# Sheet1.net
KiCad netlist of a schematic drawn in Altium Designer
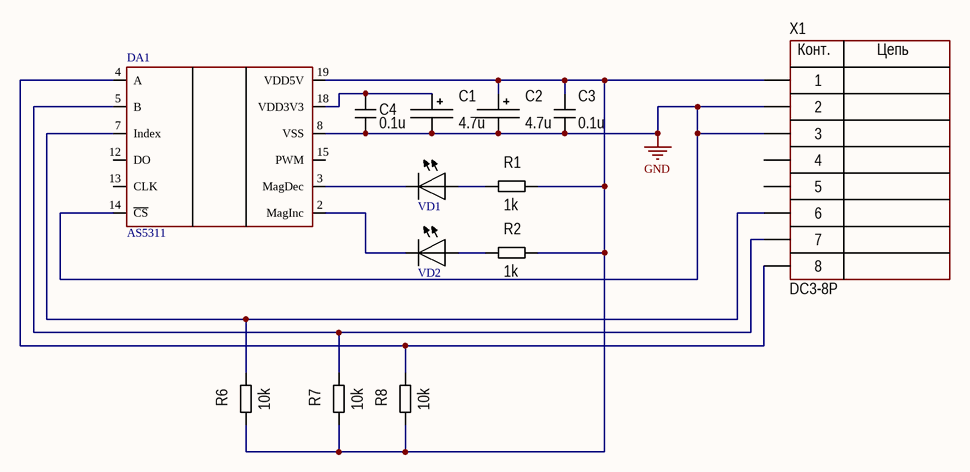
[diagram p0: Sheet1.SchDoc]

(export (version "E")
  (design (tool "Eeschema 10.0.6"))
  (components
    (comp (ref "C1")
      (value "4.7u")
      (footprint "TANTAL_A")
      (fields (field (name "MANUFACTURER") "10u"))
      (libsource (lib "Condensators") (part "TantalCap"))
    )
    (comp (ref "C2")
      (value "4.7u")
      (footprint "TANTAL_A")
      (fields (field (name "MANUFACTURER") "10u"))
      (libsource (lib "Condensators") (part "TantalCap"))
    )
    (comp (ref "C3") (value "0.1u") (footprint "CH0603C") (libsource (lib "Condensators") (part "Capacitor")))
    (comp (ref "C4") (value "0.1u") (footprint "CH0805C") (libsource (lib "Condensators") (part "Capacitor")))
    (comp (ref "DA1") (value "AS5311") (footprint "20-TSSOP") (libsource (lib "Schlib1") (part "AS5311")))
    (comp (ref "R1")
      (value "1k")
      (footprint "standard:CH0402R")
      (libsource (lib "Resistors") (part "Resistor"))
    )
    (comp (ref "R2")
      (value "1k")
      (footprint "standard:CH0402R")
      (libsource (lib "Resistors") (part "Resistor"))
    )
    (comp (ref "R6")
      (value "10k")
      (footprint "standard:CH0402R")
      (libsource (lib "Resistors") (part "Resistor"))
    )
    (comp (ref "R7")
      (value "10k")
      (footprint "standard:CH0402R")
      (libsource (lib "Resistors") (part "Resistor"))
    )
    (comp (ref "R8")
      (value "10k")
      (footprint "standard:CH0402R")
      (libsource (lib "Resistors") (part "Resistor"))
    )
    (comp (ref "VD1") (value "LED") (footprint "VD_0603") (libsource (lib "Diods") (part "LED")))
    (comp (ref "VD2") (value "LED") (footprint "VD_0603") (libsource (lib "Diods") (part "LED")))
    (comp (ref "X1")
      (value "DC3-8P")
      (footprint "CON: DC3 2x4P")
      (libsource (lib "Connectors") (part "8-Connector"))
    )
  )
  (nets
    (net (code "1") (name "GND") (class "Default")
      (node (ref "C1") (pin "2") (pinfunction "2_2") (pintype "power_in"))
      (node (ref "C2") (pin "2") (pinfunction "2_2") (pintype "power_in"))
      (node (ref "C3") (pin "1") (pinfunction "1_1") (pintype "passive"))
      (node (ref "C4") (pin "1") (pinfunction "1_1") (pintype "passive"))
      (node (ref "DA1") (pin "14") (pinfunction "~{CS}_14") (pintype "passive"))
      (node (ref "DA1") (pin "8") (pinfunction "VSS_8") (pintype "passive"))
      (node (ref "X1") (pin "2") (pinfunction "2_2") (pintype "passive"))
      (node (ref "X1") (pin "3") (pinfunction "3_3") (pintype "power_in"))
    )
    (net (code "2") (name "Net-(DA1-A)") (class "Default")
      (node (ref "DA1") (pin "4") (pinfunction "A_4") (pintype "passive"))
      (node (ref "R8") (pin "2") (pinfunction "2_2") (pintype "passive"))
      (node (ref "X1") (pin "8") (pinfunction "8_8") (pintype "power_in"))
    )
    (net (code "3") (name "Net-(DA1-B)") (class "Default")
      (node (ref "DA1") (pin "5") (pinfunction "B_5") (pintype "passive"))
      (node (ref "R7") (pin "2") (pinfunction "2_2") (pintype "passive"))
      (node (ref "X1") (pin "7") (pinfunction "7_7") (pintype "power_in"))
    )
    (net (code "4") (name "Net-(DA1-Index)") (class "Default")
      (node (ref "DA1") (pin "7") (pinfunction "Index_7") (pintype "passive"))
      (node (ref "R6") (pin "2") (pinfunction "2_2") (pintype "passive"))
      (node (ref "X1") (pin "6") (pinfunction "6_6") (pintype "power_in"))
    )
    (net (code "5") (name "Net-(DA1-MagDec)") (class "Default")
      (node (ref "DA1") (pin "3") (pinfunction "MagDec_3") (pintype "passive"))
      (node (ref "VD1") (pin "2") (pinfunction "2_2") (pintype "passive"))
    )
    (net (code "6") (name "Net-(DA1-MagInc)") (class "Default")
      (node (ref "DA1") (pin "2") (pinfunction "MagInc_2") (pintype "passive"))
      (node (ref "VD2") (pin "2") (pinfunction "2_2") (pintype "passive"))
    )
    (net (code "7") (name "Net-(DA1-VDD3V3)") (class "Default")
      (node (ref "C1") (pin "1") (pinfunction "1_1") (pintype "power_in"))
      (node (ref "C4") (pin "2") (pinfunction "2_2") (pintype "passive"))
      (node (ref "DA1") (pin "18") (pinfunction "VDD3V3_18") (pintype "passive"))
    )
    (net (code "8") (name "Net-(DA1-VDD5V)") (class "Default")
      (node (ref "C2") (pin "1") (pinfunction "1_1") (pintype "power_in"))
      (node (ref "C3") (pin "2") (pinfunction "2_2") (pintype "passive"))
      (node (ref "DA1") (pin "19") (pinfunction "VDD5V_19") (pintype "passive"))
      (node (ref "R1") (pin "2") (pinfunction "2_2") (pintype "passive"))
      (node (ref "R2") (pin "2") (pinfunction "2_2") (pintype "passive"))
      (node (ref "R6") (pin "1") (pinfunction "1_1") (pintype "passive"))
      (node (ref "R7") (pin "1") (pinfunction "1_1") (pintype "passive"))
      (node (ref "R8") (pin "1") (pinfunction "1_1") (pintype "passive"))
      (node (ref "X1") (pin "1") (pinfunction "1_1") (pintype "passive"))
    )
    (net (code "9") (name "Net-(R1-Pad1)") (class "Default")
      (node (ref "R1") (pin "1") (pinfunction "1_1") (pintype "passive"))
      (node (ref "VD1") (pin "1") (pinfunction "1_1") (pintype "passive"))
    )
    (net (code "10") (name "Net-(R2-Pad1)") (class "Default")
      (node (ref "R2") (pin "1") (pinfunction "1_1") (pintype "passive"))
      (node (ref "VD2") (pin "1") (pinfunction "1_1") (pintype "passive"))
    )
    (net (code "11") (name "unconnected-(DA1-CLK-Pad13)") (class "Default")
      (node (ref "DA1") (pin "13") (pinfunction "CLK_13") (pintype "passive"))
    )
    (net (code "12") (name "unconnected-(DA1-DO-Pad12)") (class "Default")
      (node (ref "DA1") (pin "12") (pinfunction "DO_12") (pintype "passive"))
    )
    (net (code "13") (name "unconnected-(DA1-PWM-Pad15)") (class "Default")
      (node (ref "DA1") (pin "15") (pinfunction "PWM_15") (pintype "passive"))
    )
    (net (code "14") (name "unconnected-(X1-Pad4)") (class "Default")
      (node (ref "X1") (pin "4") (pinfunction "4_4") (pintype "power_in"))
    )
    (net (code "15") (name "unconnected-(X1-Pad5)") (class "Default")
      (node (ref "X1") (pin "5") (pinfunction "5_5") (pintype "power_in"))
    )
  )
)
